# Sheet1.net
KiCad netlist of a schematic drawn in Altium Designer
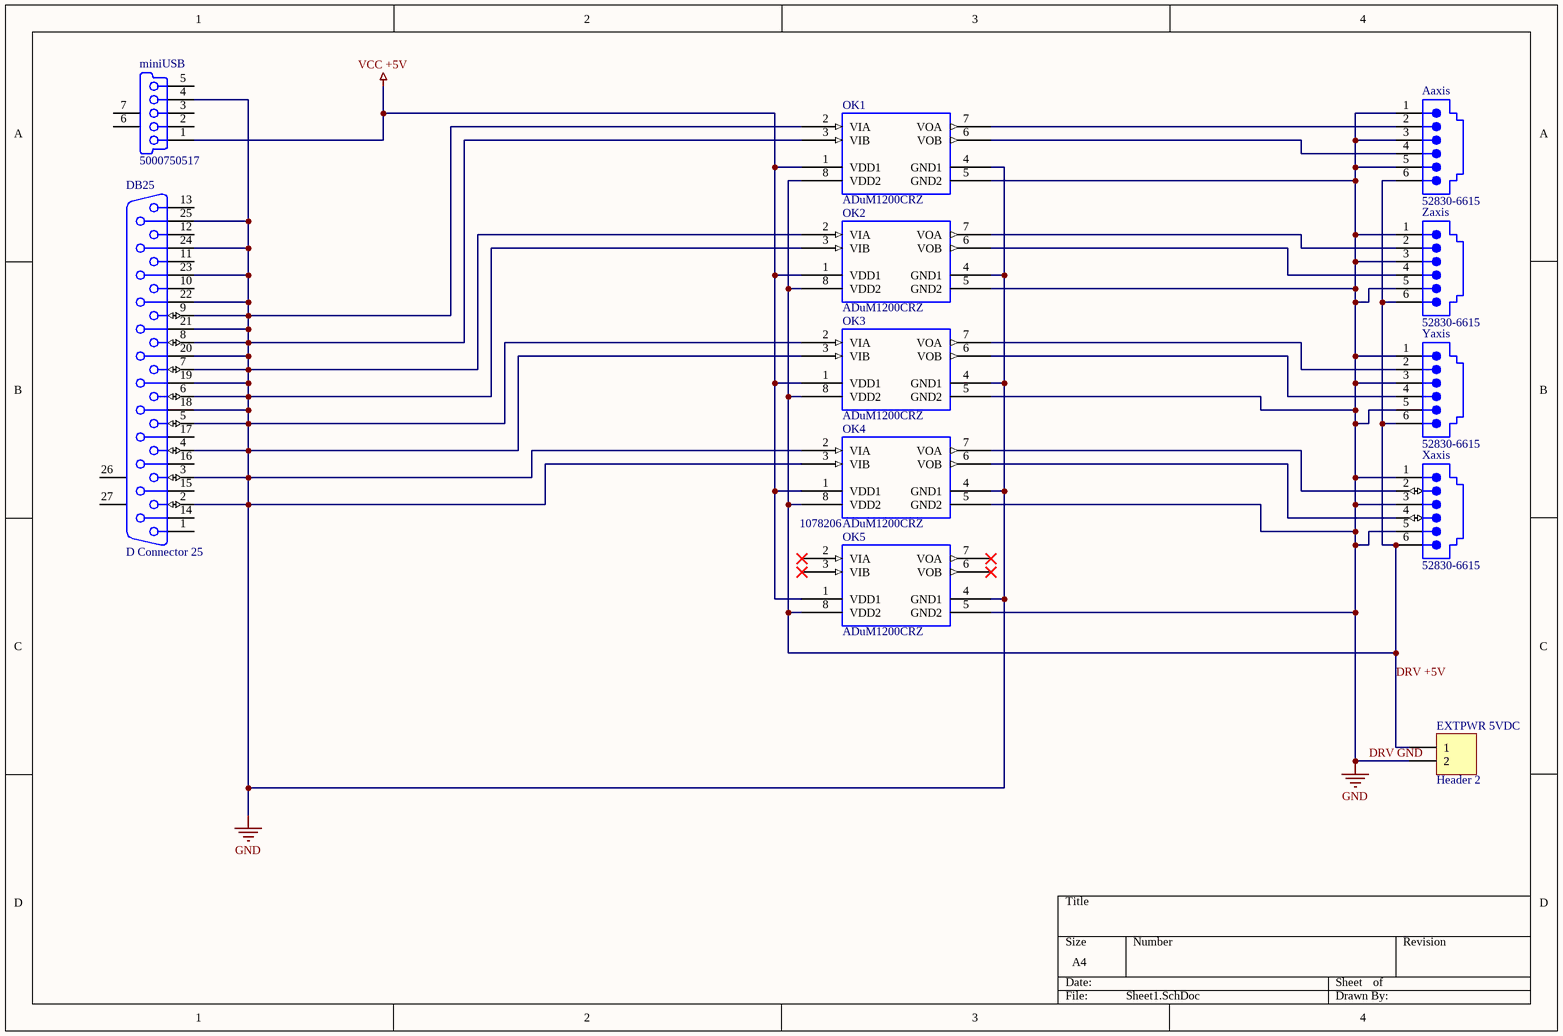
[diagram p0: Sheet1.SchDoc]

(export (version "E")
  (design (tool "Eeschema 10.0.6"))
  (components
    (comp (ref "Aaxis")
      (value "52830-6615")
      (footprint "52830-6615")
      (description "Right Angle, Standard Profile, with Metal Peg PCB Jack")
      (fields (field (name "PUBLISHER") "Altium Limited"))
      (libsource (lib "Molex Modular Jack Right Angle") (part "52830-6615"))
    )
    (comp (ref "DB25")
      (value "D Connector 25")
      (footprint "DSUB1.385-2H25A")
      (description "Receptacle Assembly, 25 Position, Right Angle")
      (fields (field (name "PUBLISHER") "Altium Limited"))
      (libsource (lib "Miscellaneous Connectors") (part "D Connector 25"))
    )
    (comp (ref "EXTPWR 5VDC")
      (value "Header 2")
      (footprint "HDR1X2")
      (description "Header, 2-Pin")
      (fields (field (name "PUBLISHER") "Altium Limited"))
      (libsource (lib "Miscellaneous Connectors") (part "Header 2"))
    )
    (comp (ref "miniUSB")
      (value "5000750517")
      (footprint "5000750517")
      (fields (field (name "PUBLISHER") "Altium Limited"))
      (libsource (lib "Molex Serial Bus Mini USB") (part "5000750517"))
    )
    (comp (ref "OK1")
      (value "ADuM1200CRZ")
      (footprint "R-8_N")
      (description "iCoupler")
      (libsource (lib "PCB_OBOB") (part "ADuM1200CRZ"))
    )
    (comp (ref "OK2")
      (value "ADuM1200CRZ")
      (footprint "R-8_N")
      (libsource (lib "PCB_OBOB") (part "ADuM1200CRZ"))
    )
    (comp (ref "OK3")
      (value "ADuM1200CRZ")
      (footprint "R-8_N")
      (libsource (lib "PCB_OBOB") (part "ADuM1200CRZ"))
    )
    (comp (ref "OK4")
      (value "ADuM1200CRZ")
      (footprint "R-8_N")
      (libsource (lib "PCB_OBOB") (part "ADuM1200CRZ"))
    )
    (comp (ref "OK5")
      (value "ADuM1200CRZ")
      (footprint "R-8_N")
      (fields (field (name "SUPPLIER PART NUMBER 1") "1078206"))
      (libsource (lib "PCB_OBOB") (part "ADuM1200CRZ"))
    )
    (comp (ref "Xaxis")
      (value "52830-6615")
      (footprint "52830-6615")
      (description "Right Angle, Standard Profile, with Metal Peg PCB Jack")
      (fields (field (name "PUBLISHER") "Altium Limited"))
      (libsource (lib "Molex Modular Jack Right Angle") (part "52830-6615"))
    )
    (comp (ref "Yaxis")
      (value "52830-6615")
      (footprint "52830-6615")
      (description "Right Angle, Standard Profile, with Metal Peg PCB Jack")
      (fields (field (name "PUBLISHER") "Altium Limited"))
      (libsource (lib "Molex Modular Jack Right Angle") (part "52830-6615"))
    )
    (comp (ref "Zaxis")
      (value "52830-6615")
      (footprint "52830-6615")
      (description "Right Angle, Standard Profile, with Metal Peg PCB Jack")
      (fields (field (name "PUBLISHER") "Altium Limited"))
      (libsource (lib "Molex Modular Jack Right Angle") (part "52830-6615"))
    )
  )
  (nets
    (net (code "1") (name "/DRV +5V") (class "Default")
      (node (ref "Aaxis") (pin "6") (pinfunction "6_6") (pintype "passive"))
      (node (ref "EXTPWR 5VDC") (pin "1") (pinfunction "1_1") (pintype "passive"))
      (node (ref "OK1") (pin "8") (pinfunction "VDD2_8") (pintype "power_in"))
      (node (ref "OK2") (pin "8") (pinfunction "VDD2_8") (pintype "power_in"))
      (node (ref "OK3") (pin "8") (pinfunction "VDD2_8") (pintype "power_in"))
      (node (ref "OK4") (pin "8") (pinfunction "VDD2_8") (pintype "power_in"))
      (node (ref "OK5") (pin "8") (pinfunction "VDD2_8") (pintype "power_in"))
      (node (ref "Xaxis") (pin "6") (pinfunction "6_6") (pintype "passive"))
      (node (ref "Yaxis") (pin "6") (pinfunction "6_6") (pintype "passive"))
      (node (ref "Zaxis") (pin "6") (pinfunction "6_6") (pintype "passive"))
    )
    (net (code "2") (name "GND") (class "Default")
      (node (ref "Aaxis") (pin "1") (pinfunction "1_1") (pintype "passive"))
      (node (ref "Aaxis") (pin "3") (pinfunction "3_3") (pintype "passive"))
      (node (ref "Aaxis") (pin "5") (pinfunction "5_5") (pintype "passive"))
      (node (ref "DB25") (pin "18") (pinfunction "18_18") (pintype "passive"))
      (node (ref "DB25") (pin "19") (pinfunction "19_19") (pintype "passive"))
      (node (ref "DB25") (pin "2") (pinfunction "2_2") (pintype "bidirectional"))
      (node (ref "DB25") (pin "20") (pinfunction "20_20") (pintype "passive"))
      (node (ref "DB25") (pin "21") (pinfunction "21_21") (pintype "passive"))
      (node (ref "DB25") (pin "22") (pinfunction "22_22") (pintype "passive"))
      (node (ref "DB25") (pin "23") (pinfunction "23_23") (pintype "passive"))
      (node (ref "DB25") (pin "24") (pinfunction "24_24") (pintype "passive"))
      (node (ref "DB25") (pin "25") (pinfunction "25_25") (pintype "passive"))
      (node (ref "DB25") (pin "3") (pinfunction "3_3") (pintype "bidirectional"))
      (node (ref "DB25") (pin "4") (pinfunction "4_4") (pintype "bidirectional"))
      (node (ref "DB25") (pin "5") (pinfunction "5_5") (pintype "bidirectional"))
      (node (ref "DB25") (pin "6") (pinfunction "6_6") (pintype "bidirectional"))
      (node (ref "DB25") (pin "7") (pinfunction "7_7") (pintype "bidirectional"))
      (node (ref "DB25") (pin "8") (pinfunction "8_8") (pintype "bidirectional"))
      (node (ref "DB25") (pin "9") (pinfunction "9_9") (pintype "bidirectional"))
      (node (ref "EXTPWR 5VDC") (pin "2") (pinfunction "2_2") (pintype "passive"))
      (node (ref "OK1") (pin "2") (pinfunction "VIA_2") (pintype "input"))
      (node (ref "OK1") (pin "3") (pinfunction "VIB_3") (pintype "input"))
      (node (ref "OK1") (pin "4") (pinfunction "GND1_4") (pintype "power_in"))
      (node (ref "OK1") (pin "5") (pinfunction "GND2_5") (pintype "power_in"))
      (node (ref "OK2") (pin "2") (pinfunction "VIA_2") (pintype "input"))
      (node (ref "OK2") (pin "3") (pinfunction "VIB_3") (pintype "input"))
      (node (ref "OK2") (pin "4") (pinfunction "GND1_4") (pintype "power_in"))
      (node (ref "OK2") (pin "5") (pinfunction "GND2_5") (pintype "power_in"))
      (node (ref "OK3") (pin "2") (pinfunction "VIA_2") (pintype "input"))
      (node (ref "OK3") (pin "3") (pinfunction "VIB_3") (pintype "input"))
      (node (ref "OK3") (pin "4") (pinfunction "GND1_4") (pintype "power_in"))
      (node (ref "OK3") (pin "5") (pinfunction "GND2_5") (pintype "power_in"))
      (node (ref "OK4") (pin "2") (pinfunction "VIA_2") (pintype "input"))
      (node (ref "OK4") (pin "3") (pinfunction "VIB_3") (pintype "input"))
      (node (ref "OK4") (pin "4") (pinfunction "GND1_4") (pintype "power_in"))
      (node (ref "OK4") (pin "5") (pinfunction "GND2_5") (pintype "power_in"))
      (node (ref "OK5") (pin "4") (pinfunction "GND1_4") (pintype "power_in"))
      (node (ref "OK5") (pin "5") (pinfunction "GND2_5") (pintype "power_in"))
      (node (ref "Xaxis") (pin "1") (pinfunction "1_1") (pintype "passive"))
      (node (ref "Xaxis") (pin "3") (pinfunction "3_3") (pintype "passive"))
      (node (ref "Xaxis") (pin "5") (pinfunction "5_5") (pintype "passive"))
      (node (ref "Yaxis") (pin "1") (pinfunction "1_1") (pintype "passive"))
      (node (ref "Yaxis") (pin "3") (pinfunction "3_3") (pintype "passive"))
      (node (ref "Yaxis") (pin "5") (pinfunction "5_5") (pintype "passive"))
      (node (ref "Zaxis") (pin "1") (pinfunction "1_1") (pintype "passive"))
      (node (ref "Zaxis") (pin "3") (pinfunction "3_3") (pintype "passive"))
      (node (ref "Zaxis") (pin "5") (pinfunction "5_5") (pintype "passive"))
      (node (ref "miniUSB") (pin "4") (pinfunction "ID_4") (pintype "passive"))
    )
    (net (code "3") (name "Net-(OK1-VOA)") (class "Default")
      (node (ref "Aaxis") (pin "2") (pinfunction "2_2") (pintype "passive"))
      (node (ref "OK1") (pin "7") (pinfunction "VOA_7") (pintype "output"))
    )
    (net (code "4") (name "Net-(OK1-VOB)") (class "Default")
      (node (ref "Aaxis") (pin "4") (pinfunction "4_4") (pintype "passive"))
      (node (ref "OK1") (pin "6") (pinfunction "VOB_6") (pintype "output"))
    )
    (net (code "5") (name "Net-(OK2-VOA)") (class "Default")
      (node (ref "OK2") (pin "7") (pinfunction "VOA_7") (pintype "output"))
      (node (ref "Zaxis") (pin "2") (pinfunction "2_2") (pintype "passive"))
    )
    (net (code "6") (name "Net-(OK2-VOB)") (class "Default")
      (node (ref "OK2") (pin "6") (pinfunction "VOB_6") (pintype "output"))
      (node (ref "Zaxis") (pin "4") (pinfunction "4_4") (pintype "passive"))
    )
    (net (code "7") (name "Net-(OK3-VOA)") (class "Default")
      (node (ref "OK3") (pin "7") (pinfunction "VOA_7") (pintype "output"))
      (node (ref "Yaxis") (pin "2") (pinfunction "2_2") (pintype "passive"))
    )
    (net (code "8") (name "Net-(OK3-VOB)") (class "Default")
      (node (ref "OK3") (pin "6") (pinfunction "VOB_6") (pintype "output"))
      (node (ref "Yaxis") (pin "4") (pinfunction "4_4") (pintype "passive"))
    )
    (net (code "9") (name "Net-(OK4-VOA)") (class "Default")
      (node (ref "OK4") (pin "7") (pinfunction "VOA_7") (pintype "output"))
      (node (ref "Xaxis") (pin "2") (pinfunction "2_2") (pintype "passive"))
    )
    (net (code "10") (name "Net-(OK4-VOB)") (class "Default")
      (node (ref "OK4") (pin "6") (pinfunction "VOB_6") (pintype "output"))
      (node (ref "Xaxis") (pin "4") (pinfunction "4_4") (pintype "passive"))
    )
    (net (code "11") (name "VCC +5V") (class "Default")
      (node (ref "OK1") (pin "1") (pinfunction "VDD1_1") (pintype "power_in"))
      (node (ref "OK2") (pin "1") (pinfunction "VDD1_1") (pintype "power_in"))
      (node (ref "OK3") (pin "1") (pinfunction "VDD1_1") (pintype "power_in"))
      (node (ref "OK4") (pin "1") (pinfunction "VDD1_1") (pintype "power_in"))
      (node (ref "OK5") (pin "1") (pinfunction "VDD1_1") (pintype "power_in"))
      (node (ref "miniUSB") (pin "1") (pinfunction "V_BUS_1") (pintype "passive"))
    )
    (net (code "12") (name "unconnected-(DB25-MH1-Pad26)") (class "Default")
      (node (ref "DB25") (pin "26") (pinfunction "MH1_26") (pintype "passive"))
    )
    (net (code "13") (name "unconnected-(DB25-MH2-Pad27)") (class "Default")
      (node (ref "DB25") (pin "27") (pinfunction "MH2_27") (pintype "passive"))
    )
    (net (code "14") (name "unconnected-(DB25-Pad1)") (class "Default")
      (node (ref "DB25") (pin "1") (pinfunction "1_1") (pintype "passive"))
    )
    (net (code "15") (name "unconnected-(DB25-Pad10)") (class "Default")
      (node (ref "DB25") (pin "10") (pinfunction "10_10") (pintype "passive"))
    )
    (net (code "16") (name "unconnected-(DB25-Pad11)") (class "Default")
      (node (ref "DB25") (pin "11") (pinfunction "11_11") (pintype "passive"))
    )
    (net (code "17") (name "unconnected-(DB25-Pad12)") (class "Default")
      (node (ref "DB25") (pin "12") (pinfunction "12_12") (pintype "passive"))
    )
    (net (code "18") (name "unconnected-(DB25-Pad13)") (class "Default")
      (node (ref "DB25") (pin "13") (pinfunction "13_13") (pintype "passive"))
    )
    (net (code "19") (name "unconnected-(DB25-Pad14)") (class "Default")
      (node (ref "DB25") (pin "14") (pinfunction "14_14") (pintype "passive"))
    )
    (net (code "20") (name "unconnected-(DB25-Pad15)") (class "Default")
      (node (ref "DB25") (pin "15") (pinfunction "15_15") (pintype "passive"))
    )
    (net (code "21") (name "unconnected-(DB25-Pad16)") (class "Default")
      (node (ref "DB25") (pin "16") (pinfunction "16_16") (pintype "passive"))
    )
    (net (code "22") (name "unconnected-(DB25-Pad17)") (class "Default")
      (node (ref "DB25") (pin "17") (pinfunction "17_17") (pintype "passive"))
    )
    (net (code "23") (name "unconnected-(OK5-VIA-Pad2)") (class "Default")
      (node (ref "OK5") (pin "2") (pinfunction "VIA_2") (pintype "input+no_connect"))
    )
    (net (code "24") (name "unconnected-(OK5-VIB-Pad3)") (class "Default")
      (node (ref "OK5") (pin "3") (pinfunction "VIB_3") (pintype "input+no_connect"))
    )
    (net (code "25") (name "unconnected-(OK5-VOA-Pad7)") (class "Default")
      (node (ref "OK5") (pin "7") (pinfunction "VOA_7") (pintype "output+no_connect"))
    )
    (net (code "26") (name "unconnected-(OK5-VOB-Pad6)") (class "Default")
      (node (ref "OK5") (pin "6") (pinfunction "VOB_6") (pintype "output+no_connect"))
    )
    (net (code "27") (name "unconnected-(miniUSB-D+-Pad3)") (class "Default")
      (node (ref "miniUSB") (pin "3") (pinfunction "D+_3") (pintype "passive"))
    )
    (net (code "28") (name "unconnected-(miniUSB-D--Pad2)") (class "Default")
      (node (ref "miniUSB") (pin "2") (pinfunction "D-_2") (pintype "passive"))
    )
    (net (code "29") (name "unconnected-(miniUSB-GND-Pad5)") (class "Default")
      (node (ref "miniUSB") (pin "5") (pinfunction "GND_5") (pintype "passive"))
    )
    (net (code "30") (name "unconnected-(miniUSB-MH1-Pad6)") (class "Default")
      (node (ref "miniUSB") (pin "6") (pinfunction "MH1_6") (pintype "passive"))
    )
    (net (code "31") (name "unconnected-(miniUSB-MH2-Pad7)") (class "Default")
      (node (ref "miniUSB") (pin "7") (pinfunction "MH2_7") (pintype "passive"))
    )
  )
)
